# TimingTesterV1.net
KiCad netlist of a schematic drawn in EAGLE
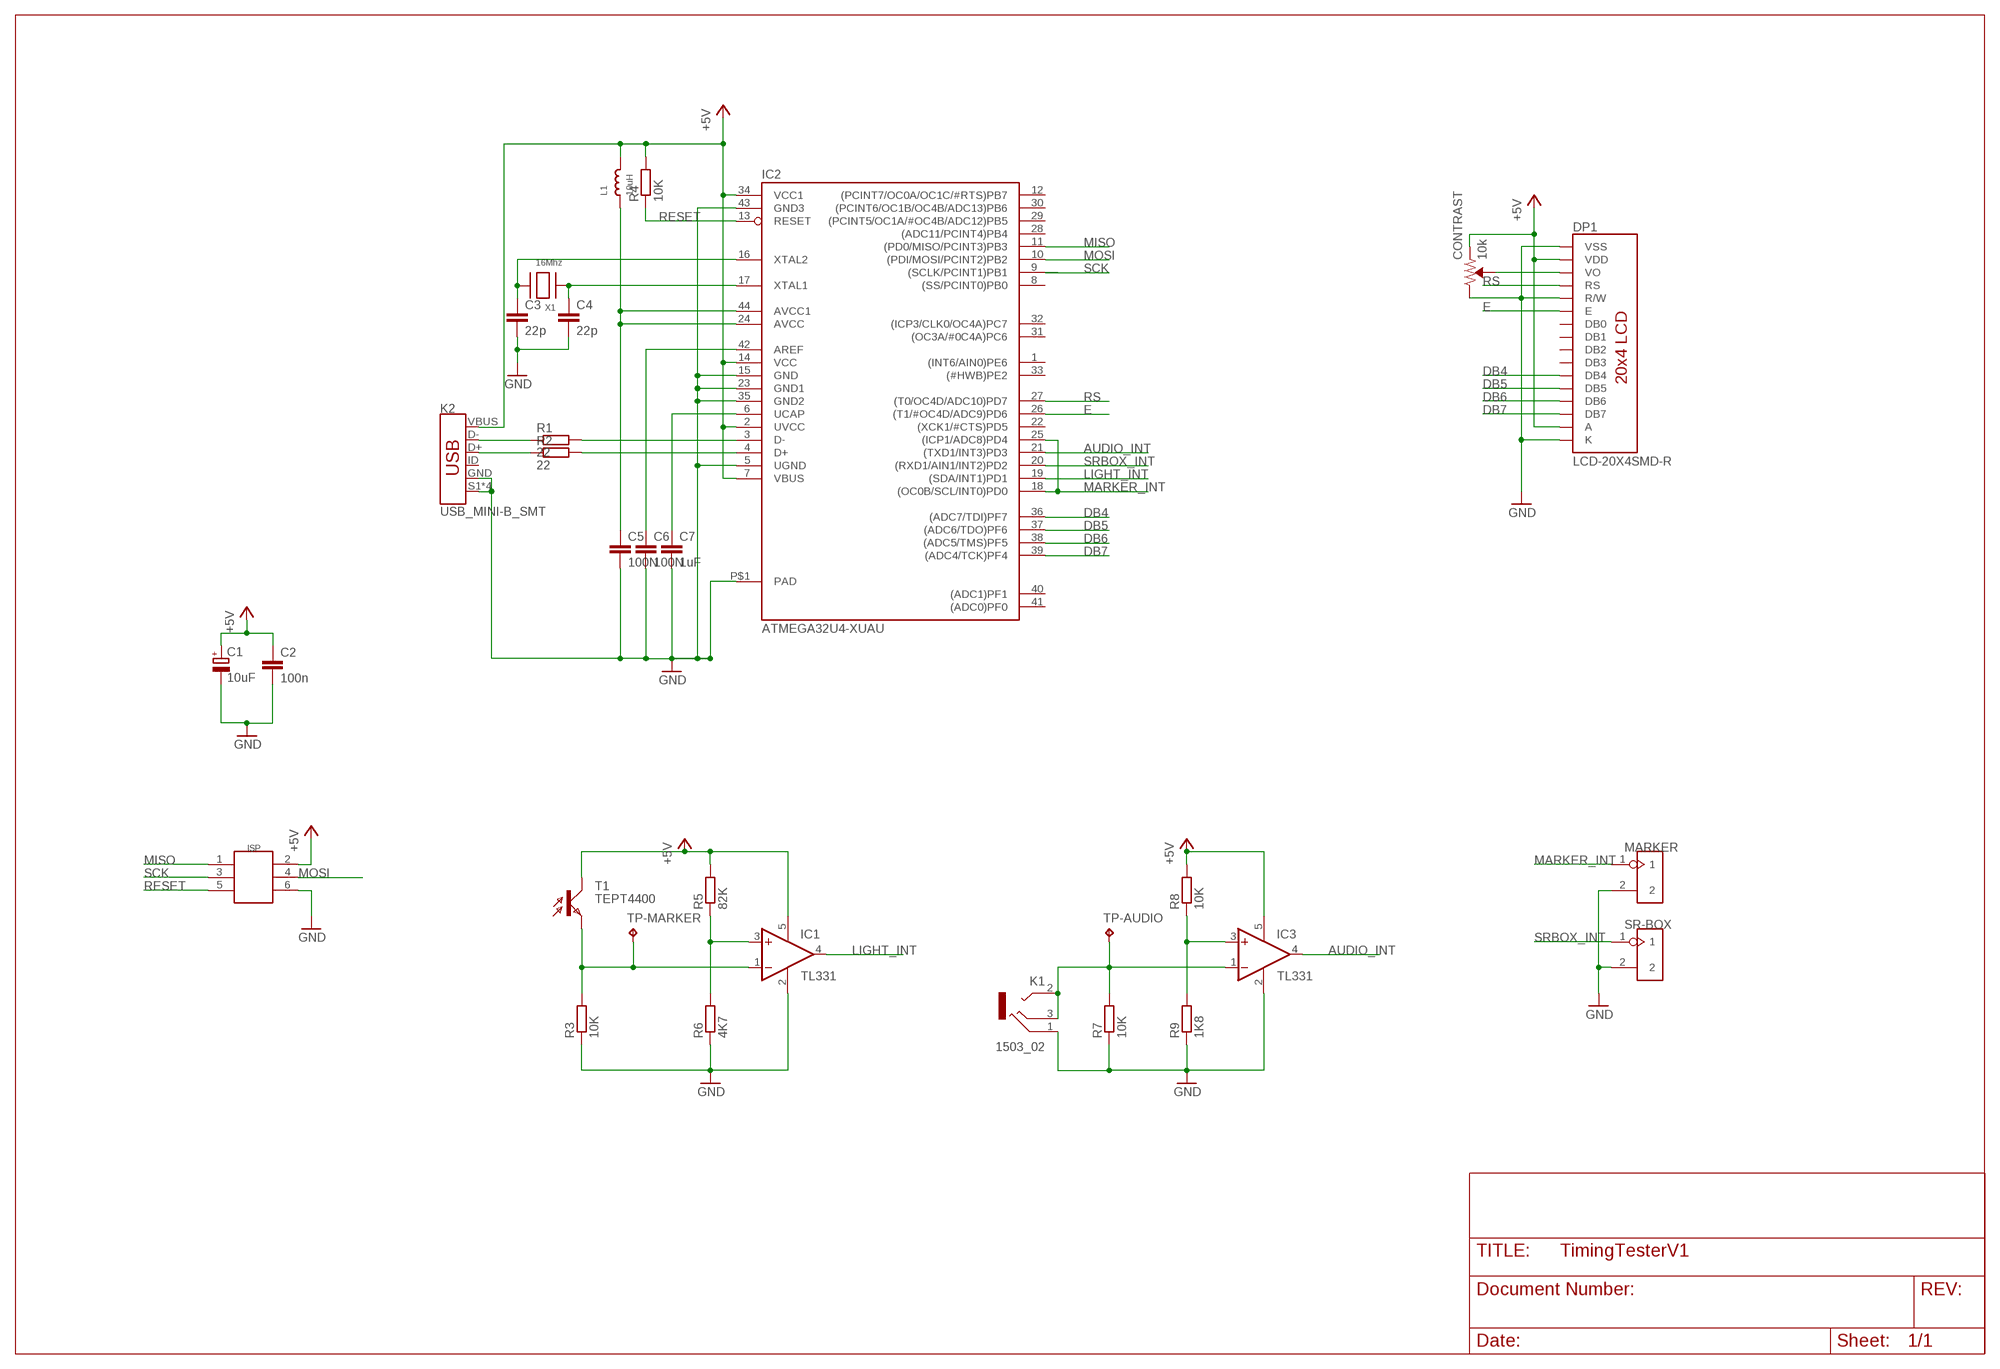
[diagram p0: schematic, sheet 1]

(export (version "E")
  (design (tool "Eeschema 10.0.6"))
  (components
    (comp (ref "C1")
      (value "10uF")
      (footprint "eagle-import:R_2012-12R")
      (libsource (lib "eagle-import") (part "CPOL-EUR/2012-12R"))
    )
    (comp (ref "C2")
      (value "100n")
      (footprint "eagle-import:C0805")
      (libsource (lib "eagle-import") (part "C-EUC0805"))
    )
    (comp (ref "C3")
      (value "22p")
      (footprint "eagle-import:C0805")
      (libsource (lib "eagle-import") (part "C-EUC0805"))
    )
    (comp (ref "C4")
      (value "22p")
      (footprint "eagle-import:C0805")
      (libsource (lib "eagle-import") (part "C-EUC0805"))
    )
    (comp (ref "C5")
      (value "100N")
      (footprint "eagle-import:C0805")
      (libsource (lib "eagle-import") (part "C-EUC0805"))
    )
    (comp (ref "C6")
      (value "100N")
      (footprint "eagle-import:C0805")
      (libsource (lib "eagle-import") (part "C-EUC0805"))
    )
    (comp (ref "C7")
      (value "1uF")
      (footprint "eagle-import:C0805")
      (libsource (lib "eagle-import") (part "C-EUC0805"))
    )
    (comp (ref "CONTRAST")
      (value "10k")
      (footprint "eagle-import:TRIMPOT-SMD-TC33X")
      (libsource (lib "eagle-import") (part "TRIMPOT-SMD-3MM-OPEN-1/10W-25%"))
    )
    (comp (ref "DP1")
      (value "LCD-20X4SMD-R")
      (footprint "eagle-import:LCD-20X4-SMD")
      (libsource (lib "eagle-import") (part "LCD-20X4SMD-R"))
    )
    (comp (ref "IC1")
      (value "TL331")
      (footprint "eagle-import:DBV-R-PDSO-G5")
      (libsource (lib "eagle-import") (part "TL331"))
    )
    (comp (ref "IC2")
      (value "ATMEGA32U4-XUAU")
      (footprint "eagle-import:TQFP44-PAD")
      (libsource (lib "eagle-import") (part "ATMEGA32U4-XUAU"))
    )
    (comp (ref "IC3")
      (value "TL331")
      (footprint "eagle-import:DBV-R-PDSO-G5")
      (libsource (lib "eagle-import") (part "TL331"))
    )
    (comp (ref "ISP")
      (value "HEADER-2X3P-SMD")
      (footprint "eagle-import:2X3P-2.54-SMD")
      (libsource (lib "eagle-import") (part "HEADER-2X3P-SMD"))
    )
    (comp (ref "K1")
      (value "1503_02")
      (footprint "eagle-import:1503_02")
      (libsource (lib "eagle-import") (part "1503_02"))
    )
    (comp (ref "K2")
      (value "USB_MINI-B_SMT")
      (footprint "eagle-import:USB-MINIB")
      (libsource (lib "eagle-import") (part "USB_MINI-B_SMT"))
    )
    (comp (ref "L1")
      (value "10uH")
      (footprint "eagle-import:0805")
      (libsource (lib "eagle-import") (part "INDUCTOR0805"))
    )
    (comp (ref "MARKER")
      (value "HEADER-2PSMD")
      (footprint "eagle-import:2P-2.54-SMD")
      (libsource (lib "eagle-import") (part "HEADER-2PSMD"))
    )
    (comp (ref "R1")
      (value "22")
      (footprint "eagle-import:M0805")
      (libsource (lib "eagle-import") (part "R-EU_M0805"))
    )
    (comp (ref "R2")
      (value "22")
      (footprint "eagle-import:M0805")
      (libsource (lib "eagle-import") (part "R-EU_M0805"))
    )
    (comp (ref "R3")
      (value "10K")
      (footprint "eagle-import:R0603")
      (libsource (lib "eagle-import") (part "R-EU_R0603"))
    )
    (comp (ref "R4")
      (value "10K")
      (footprint "eagle-import:M0805")
      (libsource (lib "eagle-import") (part "R-EU_M0805"))
    )
    (comp (ref "R5")
      (value "82K")
      (footprint "eagle-import:R0603")
      (libsource (lib "eagle-import") (part "R-EU_R0603"))
    )
    (comp (ref "R6")
      (value "4K7")
      (footprint "eagle-import:R0603")
      (libsource (lib "eagle-import") (part "R-EU_R0603"))
    )
    (comp (ref "R7")
      (value "10K")
      (footprint "eagle-import:R0603")
      (libsource (lib "eagle-import") (part "R-EU_R0603"))
    )
    (comp (ref "R8")
      (value "10K")
      (footprint "eagle-import:R0603")
      (libsource (lib "eagle-import") (part "R-EU_R0603"))
    )
    (comp (ref "R9")
      (value "1K8")
      (footprint "eagle-import:R0603")
      (libsource (lib "eagle-import") (part "R-EU_R0603"))
    )
    (comp (ref "SR-BOX")
      (value "HEADER-2PSMD")
      (footprint "eagle-import:2P-2.54-SMD")
      (libsource (lib "eagle-import") (part "HEADER-2PSMD"))
    )
    (comp (ref "T1")
      (value "TEPT4400")
      (footprint "eagle-import:BPX81-SMD")
      (libsource (lib "eagle-import") (part "BPX81SMD"))
    )
    (comp (ref "TP-AUDIO")
      (value "TPTP20R")
      (footprint "eagle-import:TP20R")
      (libsource (lib "eagle-import") (part "TPTP20R"))
    )
    (comp (ref "TP-MARKER")
      (value "TPTP20R")
      (footprint "eagle-import:TP20R")
      (libsource (lib "eagle-import") (part "TPTP20R"))
    )
    (comp (ref "X1")
      (value "16Mhz")
      (footprint "eagle-import:NX5032")
      (libsource (lib "eagle-import") (part "XTALNX5032"))
    )
  )
  (nets
    (net (code "1") (name "+5V") (class "Default")
      (node (ref "C1") (pin "+") (pinfunction "+_+") (pintype "passive"))
      (node (ref "C2") (pin "2") (pinfunction "2_2") (pintype "passive"))
      (node (ref "CONTRAST") (pin "3") (pinfunction "CCW_3") (pintype "passive"))
      (node (ref "DP1") (pin "15") (pinfunction "A_15") (pintype "power_in"))
      (node (ref "DP1") (pin "2") (pinfunction "VDD_2") (pintype "power_in"))
      (node (ref "IC1") (pin "5") (pinfunction "V+_5") (pintype "power_in"))
      (node (ref "IC2") (pin "14") (pinfunction "VCC_14") (pintype "power_in"))
      (node (ref "IC2") (pin "2") (pinfunction "UVCC_2") (pintype "power_in"))
      (node (ref "IC2") (pin "34") (pinfunction "VCC1_34") (pintype "power_in"))
      (node (ref "IC2") (pin "7") (pinfunction "VBUS_7") (pintype "input"))
      (node (ref "IC3") (pin "5") (pinfunction "V+_5") (pintype "power_in"))
      (node (ref "ISP") (pin "2") (pinfunction "2_2") (pintype "bidirectional"))
      (node (ref "K2") (pin "VBUS") (pinfunction "VBUS_VBUS") (pintype "power_in"))
      (node (ref "L1") (pin "2") (pinfunction "2_2") (pintype "passive"))
      (node (ref "R4") (pin "2") (pinfunction "2_2") (pintype "passive"))
      (node (ref "R5") (pin "2") (pinfunction "2_2") (pintype "passive"))
      (node (ref "R8") (pin "2") (pinfunction "2_2") (pintype "passive"))
      (node (ref "T1") (pin "C") (pinfunction "C_C") (pintype "passive"))
    )
    (net (code "2") (name "/AUDIO_INT") (class "Default")
      (node (ref "IC2") (pin "21") (pinfunction "(TXD1/INT3)PD3_21") (pintype "bidirectional"))
      (node (ref "IC3") (pin "4") (pinfunction "OUT_4") (pintype "output"))
    )
    (net (code "3") (name "/DB4") (class "Default")
      (node (ref "DP1") (pin "11") (pinfunction "DB4_11") (pintype "bidirectional"))
      (node (ref "IC2") (pin "36") (pinfunction "(ADC7/TDI)PF7_36") (pintype "bidirectional"))
    )
    (net (code "4") (name "/DB5") (class "Default")
      (node (ref "DP1") (pin "12") (pinfunction "DB5_12") (pintype "bidirectional"))
      (node (ref "IC2") (pin "37") (pinfunction "(ADC6/TDO)PF6_37") (pintype "bidirectional"))
    )
    (net (code "5") (name "/DB6") (class "Default")
      (node (ref "DP1") (pin "13") (pinfunction "DB6_13") (pintype "bidirectional"))
      (node (ref "IC2") (pin "38") (pinfunction "(ADC5/TMS)PF5_38") (pintype "bidirectional"))
    )
    (net (code "6") (name "/DB7") (class "Default")
      (node (ref "DP1") (pin "14") (pinfunction "DB7_14") (pintype "bidirectional"))
      (node (ref "IC2") (pin "39") (pinfunction "(ADC4/TCK)PF4_39") (pintype "bidirectional"))
    )
    (net (code "7") (name "/E") (class "Default")
      (node (ref "DP1") (pin "6") (pinfunction "E_6") (pintype "input"))
      (node (ref "IC2") (pin "26") (pinfunction "(T1/#OC4D/ADC9)PD6_26") (pintype "bidirectional"))
    )
    (net (code "8") (name "/LIGHT_INT") (class "Default")
      (node (ref "IC1") (pin "4") (pinfunction "OUT_4") (pintype "output"))
      (node (ref "IC2") (pin "19") (pinfunction "(SDA/INT1)PD1_19") (pintype "bidirectional"))
    )
    (net (code "9") (name "/MARKER_INT") (class "Default")
      (node (ref "IC2") (pin "18") (pinfunction "(OC0B/SCL/INT0)PD0_18") (pintype "bidirectional"))
      (node (ref "IC2") (pin "25") (pinfunction "(ICP1/ADC8)PD4_25") (pintype "bidirectional"))
      (node (ref "MARKER") (pin "1") (pinfunction "1_1") (pintype "bidirectional"))
    )
    (net (code "10") (name "/MISO") (class "Default")
      (node (ref "IC2") (pin "11") (pinfunction "(PD0/MISO/PCINT3)PB3_11") (pintype "bidirectional"))
      (node (ref "ISP") (pin "1") (pinfunction "1_1") (pintype "bidirectional"))
    )
    (net (code "11") (name "/MOSI") (class "Default")
      (node (ref "IC2") (pin "10") (pinfunction "(PDI/MOSI/PCINT2)PB2_10") (pintype "bidirectional"))
      (node (ref "ISP") (pin "4") (pinfunction "4_4") (pintype "bidirectional"))
    )
    (net (code "12") (name "/RESET") (class "Default")
      (node (ref "IC2") (pin "13") (pinfunction "RESET_13") (pintype "input"))
      (node (ref "ISP") (pin "5") (pinfunction "5_5") (pintype "bidirectional"))
      (node (ref "R4") (pin "1") (pinfunction "1_1") (pintype "passive"))
    )
    (net (code "13") (name "/RS") (class "Default")
      (node (ref "DP1") (pin "4") (pinfunction "RS_4") (pintype "input"))
      (node (ref "IC2") (pin "27") (pinfunction "(T0/OC4D/ADC10)PD7_27") (pintype "bidirectional"))
    )
    (net (code "14") (name "/SCK") (class "Default")
      (node (ref "IC2") (pin "9") (pinfunction "(SCLK/PCINT1)PB1_9") (pintype "bidirectional"))
      (node (ref "ISP") (pin "3") (pinfunction "3_3") (pintype "bidirectional"))
    )
    (net (code "15") (name "/SRBOX_INT") (class "Default")
      (node (ref "IC2") (pin "20") (pinfunction "(RXD1/AIN1/INT2)PD2_20") (pintype "bidirectional"))
      (node (ref "SR-BOX") (pin "1") (pinfunction "1_1") (pintype "bidirectional"))
    )
    (net (code "16") (name "GND") (class "Default")
      (node (ref "C1") (pin "-") (pinfunction "-_-") (pintype "passive"))
      (node (ref "C2") (pin "1") (pinfunction "1_1") (pintype "passive"))
      (node (ref "C3") (pin "2") (pinfunction "2_2") (pintype "passive"))
      (node (ref "C4") (pin "2") (pinfunction "2_2") (pintype "passive"))
      (node (ref "C5") (pin "2") (pinfunction "2_2") (pintype "passive"))
      (node (ref "C6") (pin "2") (pinfunction "2_2") (pintype "passive"))
      (node (ref "C7") (pin "2") (pinfunction "2_2") (pintype "passive"))
      (node (ref "CONTRAST") (pin "1") (pinfunction "CW_1") (pintype "passive"))
      (node (ref "DP1") (pin "1") (pinfunction "VSS_1") (pintype "power_in"))
      (node (ref "DP1") (pin "16") (pinfunction "K_16") (pintype "power_in"))
      (node (ref "DP1") (pin "5") (pinfunction "R/W_5") (pintype "input"))
      (node (ref "IC1") (pin "2") (pinfunction "GND_2") (pintype "power_in"))
      (node (ref "IC2") (pin "15") (pinfunction "GND_15") (pintype "power_in"))
      (node (ref "IC2") (pin "23") (pinfunction "GND1_23") (pintype "power_in"))
      (node (ref "IC2") (pin "35") (pinfunction "GND2_35") (pintype "power_in"))
      (node (ref "IC2") (pin "43") (pinfunction "GND3_43") (pintype "power_in"))
      (node (ref "IC2") (pin "5") (pinfunction "UGND_5") (pintype "power_in"))
      (node (ref "IC2") (pin "P$1") (pinfunction "PAD_P$1") (pintype "power_in"))
      (node (ref "IC3") (pin "2") (pinfunction "GND_2") (pintype "power_in"))
      (node (ref "ISP") (pin "6") (pinfunction "6_6") (pintype "bidirectional"))
      (node (ref "K1") (pin "1") (pinfunction "1_1") (pintype "passive"))
      (node (ref "K2") (pin "GND") (pinfunction "GND_GND") (pintype "power_in"))
      (node (ref "K2") (pin "S1") (pinfunction "SHIELD_S1") (pintype "bidirectional"))
      (node (ref "K2") (pin "S2") (pinfunction "SHIELD_S2") (pintype "bidirectional"))
      (node (ref "K2") (pin "S3") (pinfunction "SHIELD_S3") (pintype "bidirectional"))
      (node (ref "K2") (pin "S4") (pinfunction "SHIELD_S4") (pintype "bidirectional"))
      (node (ref "MARKER") (pin "2") (pinfunction "2_2") (pintype "bidirectional"))
      (node (ref "R3") (pin "1") (pinfunction "1_1") (pintype "passive"))
      (node (ref "R6") (pin "1") (pinfunction "1_1") (pintype "passive"))
      (node (ref "R7") (pin "1") (pinfunction "1_1") (pintype "passive"))
      (node (ref "R9") (pin "1") (pinfunction "1_1") (pintype "passive"))
      (node (ref "SR-BOX") (pin "2") (pinfunction "2_2") (pintype "bidirectional"))
    )
    (net (code "17") (name "Net-(CONTRAST-WIPER)") (class "Default")
      (node (ref "CONTRAST") (pin "2") (pinfunction "WIPER_2") (pintype "passive"))
      (node (ref "DP1") (pin "3") (pinfunction "VO_3") (pintype "bidirectional"))
    )
    (net (code "18") (name "Net-(IC1-+IN)") (class "Default")
      (node (ref "IC1") (pin "3") (pinfunction "+IN_3") (pintype "input"))
      (node (ref "R5") (pin "1") (pinfunction "1_1") (pintype "passive"))
      (node (ref "R6") (pin "2") (pinfunction "2_2") (pintype "passive"))
    )
    (net (code "19") (name "Net-(IC1--IN)") (class "Default")
      (node (ref "IC1") (pin "1") (pinfunction "-IN_1") (pintype "input"))
      (node (ref "R3") (pin "2") (pinfunction "2_2") (pintype "passive"))
      (node (ref "T1") (pin "E") (pinfunction "E_E") (pintype "passive"))
      (node (ref "TP-MARKER") (pin "TP") (pinfunction "TP_TP") (pintype "input"))
    )
    (net (code "20") (name "Net-(IC2-AREF)") (class "Default")
      (node (ref "C6") (pin "1") (pinfunction "1_1") (pintype "passive"))
      (node (ref "IC2") (pin "42") (pinfunction "AREF_42") (pintype "power_in"))
    )
    (net (code "21") (name "Net-(IC2-AVCC)") (class "Default")
      (node (ref "C5") (pin "1") (pinfunction "1_1") (pintype "passive"))
      (node (ref "IC2") (pin "24") (pinfunction "AVCC_24") (pintype "power_in"))
      (node (ref "IC2") (pin "44") (pinfunction "AVCC1_44") (pintype "power_in"))
      (node (ref "L1") (pin "1") (pinfunction "1_1") (pintype "passive"))
    )
    (net (code "22") (name "Net-(IC2-D+)") (class "Default")
      (node (ref "IC2") (pin "4") (pinfunction "D+_4") (pintype "bidirectional"))
      (node (ref "R2") (pin "2") (pinfunction "2_2") (pintype "passive"))
    )
    (net (code "23") (name "Net-(IC2-D-)") (class "Default")
      (node (ref "IC2") (pin "3") (pinfunction "D-_3") (pintype "bidirectional"))
      (node (ref "R1") (pin "2") (pinfunction "2_2") (pintype "passive"))
    )
    (net (code "24") (name "Net-(IC2-UCAP)") (class "Default")
      (node (ref "C7") (pin "1") (pinfunction "1_1") (pintype "passive"))
      (node (ref "IC2") (pin "6") (pinfunction "UCAP_6") (pintype "passive"))
    )
    (net (code "25") (name "Net-(IC2-XTAL1)") (class "Default")
      (node (ref "C4") (pin "1") (pinfunction "1_1") (pintype "passive"))
      (node (ref "IC2") (pin "17") (pinfunction "XTAL1_17") (pintype "bidirectional"))
      (node (ref "X1") (pin "P$1") (pinfunction "P$1_P$1") (pintype "bidirectional"))
    )
    (net (code "26") (name "Net-(IC2-XTAL2)") (class "Default")
      (node (ref "C3") (pin "1") (pinfunction "1_1") (pintype "passive"))
      (node (ref "IC2") (pin "16") (pinfunction "XTAL2_16") (pintype "bidirectional"))
      (node (ref "X1") (pin "P$2") (pinfunction "P$2_P$2") (pintype "bidirectional"))
    )
    (net (code "27") (name "Net-(IC3-+IN)") (class "Default")
      (node (ref "IC3") (pin "3") (pinfunction "+IN_3") (pintype "input"))
      (node (ref "R8") (pin "1") (pinfunction "1_1") (pintype "passive"))
      (node (ref "R9") (pin "2") (pinfunction "2_2") (pintype "passive"))
    )
    (net (code "28") (name "Net-(IC3--IN)") (class "Default")
      (node (ref "IC3") (pin "1") (pinfunction "-IN_1") (pintype "input"))
      (node (ref "K1") (pin "2") (pinfunction "2_2") (pintype "passive"))
      (node (ref "K1") (pin "3") (pinfunction "3_3") (pintype "passive"))
      (node (ref "R7") (pin "2") (pinfunction "2_2") (pintype "passive"))
      (node (ref "TP-AUDIO") (pin "TP") (pinfunction "TP_TP") (pintype "input"))
    )
    (net (code "29") (name "Net-(K2-PadD+)") (class "Default")
      (node (ref "K2") (pin "D+") (pinfunction "D+_D+") (pintype "bidirectional"))
      (node (ref "R2") (pin "1") (pinfunction "1_1") (pintype "passive"))
    )
    (net (code "30") (name "Net-(K2-PadD-)") (class "Default")
      (node (ref "K2") (pin "D-") (pinfunction "D-_D-") (pintype "bidirectional"))
      (node (ref "R1") (pin "1") (pinfunction "1_1") (pintype "passive"))
    )
    (net (code "31") (name "unconnected-(DP1-DB0-Pad7)") (class "Default")
      (node (ref "DP1") (pin "7") (pinfunction "DB0_7") (pintype "bidirectional"))
    )
    (net (code "32") (name "unconnected-(DP1-DB1-Pad8)") (class "Default")
      (node (ref "DP1") (pin "8") (pinfunction "DB1_8") (pintype "bidirectional"))
    )
    (net (code "33") (name "unconnected-(DP1-DB2-Pad9)") (class "Default")
      (node (ref "DP1") (pin "9") (pinfunction "DB2_9") (pintype "bidirectional"))
    )
    (net (code "34") (name "unconnected-(DP1-DB3-Pad10)") (class "Default")
      (node (ref "DP1") (pin "10") (pinfunction "DB3_10") (pintype "bidirectional"))
    )
    (net (code "35") (name "unconnected-(IC2-(#HWB)PE2-Pad33)") (class "Default")
      (node (ref "IC2") (pin "33") (pinfunction "(#HWB)PE2_33") (pintype "bidirectional"))
    )
    (net (code "36") (name "unconnected-(IC2-(ADC0)PF0-Pad41)") (class "Default")
      (node (ref "IC2") (pin "41") (pinfunction "(ADC0)PF0_41") (pintype "bidirectional"))
    )
    (net (code "37") (name "unconnected-(IC2-(ADC1)PF1-Pad40)") (class "Default")
      (node (ref "IC2") (pin "40") (pinfunction "(ADC1)PF1_40") (pintype "bidirectional"))
    )
    (net (code "38") (name "unconnected-(IC2-(ADC11{slash}PCINT4)PB4-Pad28)") (class "Default")
      (node (ref "IC2") (pin "28") (pinfunction "(ADC11/PCINT4)PB4_28") (pintype "bidirectional"))
    )
    (net (code "39") (name "unconnected-(IC2-(ICP3{slash}CLK0{slash}OC4A)PC7-Pad32)") (class "Default")
      (node (ref "IC2") (pin "32") (pinfunction "(ICP3/CLK0/OC4A)PC7_32") (pintype "bidirectional"))
    )
    (net (code "40") (name "unconnected-(IC2-(INT6{slash}AIN0)PE6-Pad1)") (class "Default")
      (node (ref "IC2") (pin "1") (pinfunction "(INT6/AIN0)PE6_1") (pintype "bidirectional"))
    )
    (net (code "41") (name "unconnected-(IC2-(OC3A{slash}#0C4A)PC6-Pad31)") (class "Default")
      (node (ref "IC2") (pin "31") (pinfunction "(OC3A/#0C4A)PC6_31") (pintype "bidirectional"))
    )
    (net (code "42") (name "unconnected-(IC2-(PCINT5{slash}OC1A{slash}#OC4B{slash}ADC12)PB5-Pad29)") (class "Default")
      (node (ref "IC2") (pin "29") (pinfunction "(PCINT5/OC1A/#OC4B/ADC12)PB5_29") (pintype "bidirectional"))
    )
    (net (code "43") (name "unconnected-(IC2-(PCINT6{slash}OC1B{slash}OC4B{slash}ADC13)PB6-Pad30)") (class "Default")
      (node (ref "IC2") (pin "30") (pinfunction "(PCINT6/OC1B/OC4B/ADC13)PB6_30") (pintype "bidirectional"))
    )
    (net (code "44") (name "unconnected-(IC2-(PCINT7{slash}OC0A{slash}OC1C{slash}#RTS)PB7-Pad12)") (class "Default")
      (node (ref "IC2") (pin "12") (pinfunction "(PCINT7/OC0A/OC1C/#RTS)PB7_12") (pintype "bidirectional"))
    )
    (net (code "45") (name "unconnected-(IC2-(SS{slash}PCINT0)PB0-Pad8)") (class "Default")
      (node (ref "IC2") (pin "8") (pinfunction "(SS/PCINT0)PB0_8") (pintype "bidirectional"))
    )
    (net (code "46") (name "unconnected-(IC2-(XCK1{slash}#CTS)PD5-Pad22)") (class "Default")
      (node (ref "IC2") (pin "22") (pinfunction "(XCK1/#CTS)PD5_22") (pintype "bidirectional"))
    )
    (net (code "47") (name "unconnected-(K1-2-Pad2@2)") (class "Default")
      (node (ref "K1") (pin "2@2") (pinfunction "2_2@2") (pintype "passive"))
    )
    (net (code "48") (name "unconnected-(K2-PadID)") (class "Default")
      (node (ref "K2") (pin "ID") (pinfunction "ID_ID") (pintype "bidirectional"))
    )
  )
)
